# HominiPulseSensor.net
KiCad netlist of a schematic drawn in EAGLE
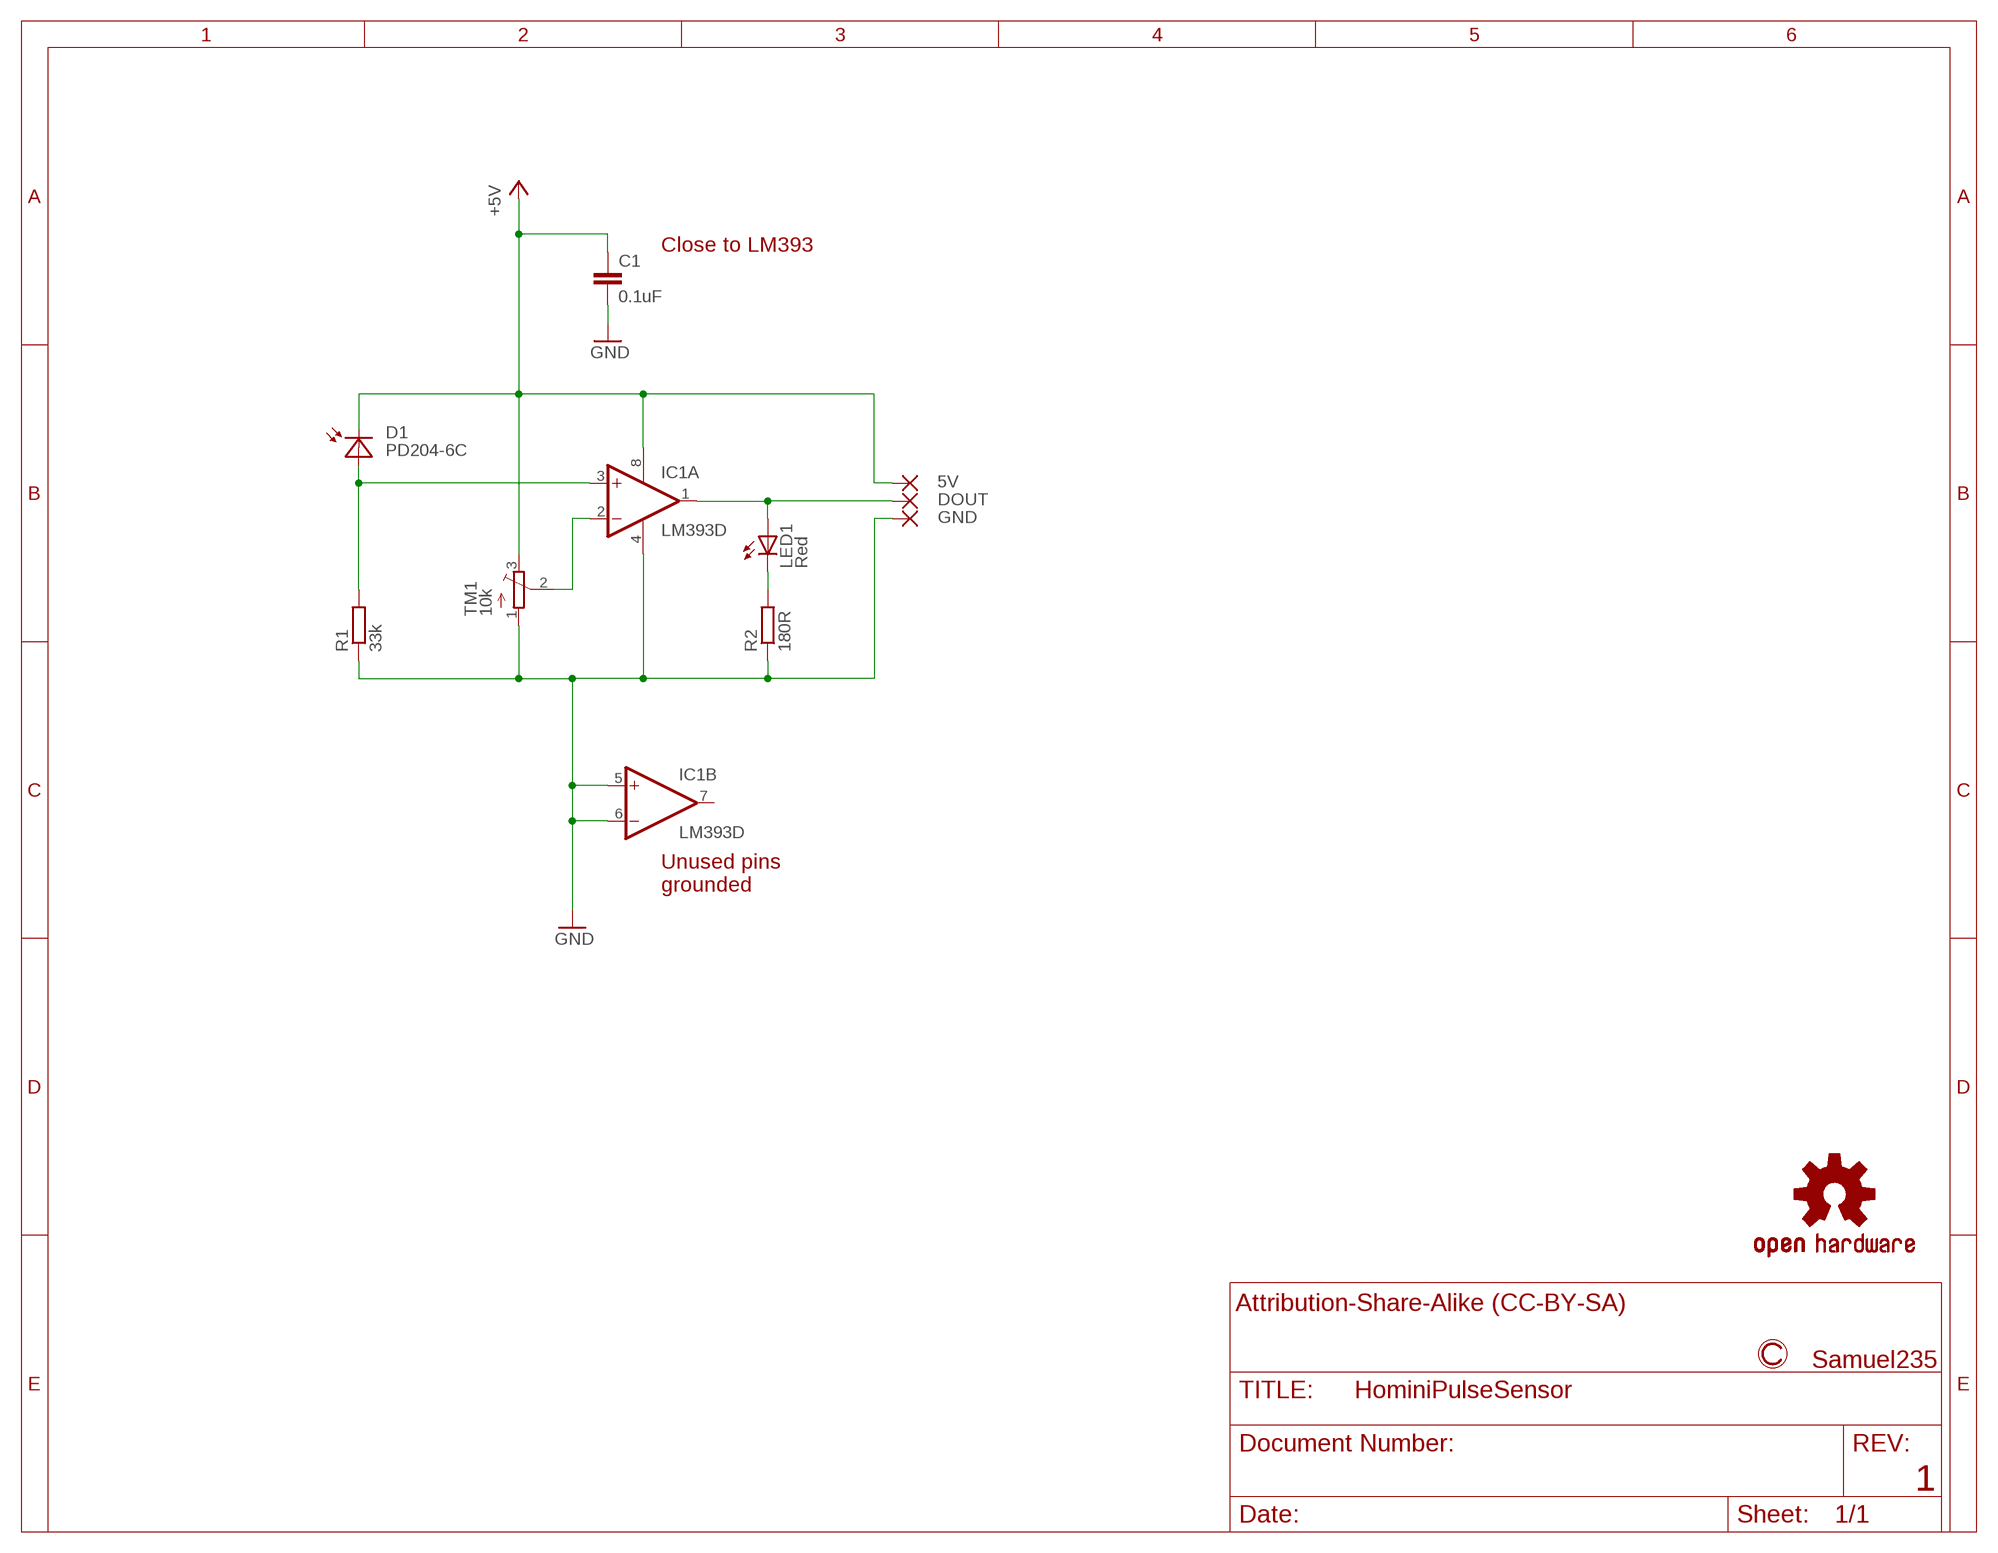
[diagram p0: schematic, sheet 1]

(export (version "E")
  (design (tool "Eeschema 10.0.6"))
  (components
    (comp (ref "5V")
      (value "SMD2")
      (footprint "eagle-import:SMD1,27-2,54")
      (libsource (lib "eagle-import") (part "SMD2"))
    )
    (comp (ref "C1")
      (value "0.1uF")
      (footprint "eagle-import:C0603")
      (libsource (lib "eagle-import") (part "C-EUC0603"))
    )
    (comp (ref "D1")
      (value "PD204-6C")
      (footprint "eagle-import:3MM-PTH")
      (libsource (lib "eagle-import") (part "PD204-6C"))
    )
    (comp (ref "DOUT")
      (value "SMD2")
      (footprint "eagle-import:SMD1,27-2,54")
      (libsource (lib "eagle-import") (part "SMD2"))
    )
    (comp (ref "GND")
      (value "SMD2")
      (footprint "eagle-import:SMD1,27-2,54")
      (libsource (lib "eagle-import") (part "SMD2"))
    )
    (comp (ref "IC1")
      (value "LM393D")
      (footprint "eagle-import:SO08")
      (libsource (lib "eagle-import") (part "LM393D"))
    )
    (comp (ref "LED1")
      (value "Red")
      (footprint "eagle-import:LED3MM")
      (libsource (lib "eagle-import") (part "LED3MM"))
    )
    (comp (ref "LOGO1")
      (value "OSHW-LOGOS")
      (footprint "eagle-import:OSHW-LOGO-S")
      (libsource (lib "eagle-import") (part "OSHW-LOGOS"))
    )
    (comp (ref "R1")
      (value "33k")
      (footprint "eagle-import:R0603")
      (libsource (lib "eagle-import") (part "R-EU_R0603"))
    )
    (comp (ref "R2")
      (value "180R")
      (footprint "eagle-import:R0603")
      (libsource (lib "eagle-import") (part "R-EU_R0603"))
    )
    (comp (ref "TM1")
      (value "10k")
      (footprint "eagle-import:TC33X")
      (libsource (lib "eagle-import") (part "TRIMPOTTC33X"))
    )
  )
  (nets
    (net (code "1") (name "+5V") (class "Default")
      (node (ref "5V") (pin "1") (pinfunction "P_1") (pintype "passive"))
      (node (ref "C1") (pin "1") (pinfunction "1_1") (pintype "passive"))
      (node (ref "D1") (pin "C") (pinfunction "C_C") (pintype "passive"))
      (node (ref "IC1") (pin "8") (pinfunction "V+_8") (pintype "power_in"))
      (node (ref "TM1") (pin "3") (pinfunction "E_3") (pintype "passive"))
    )
    (net (code "2") (name "GND") (class "Default")
      (node (ref "C1") (pin "2") (pinfunction "2_2") (pintype "passive"))
      (node (ref "GND") (pin "1") (pinfunction "P_1") (pintype "passive"))
      (node (ref "IC1") (pin "4") (pinfunction "V-_4") (pintype "power_in"))
      (node (ref "IC1") (pin "5") (pinfunction "+IN_5") (pintype "input"))
      (node (ref "IC1") (pin "6") (pinfunction "-IN_6") (pintype "input"))
      (node (ref "R1") (pin "1") (pinfunction "1_1") (pintype "passive"))
      (node (ref "R2") (pin "1") (pinfunction "1_1") (pintype "passive"))
      (node (ref "TM1") (pin "1") (pinfunction "A_1") (pintype "passive"))
    )
    (net (code "3") (name "Net-(DOUT-P)") (class "Default")
      (node (ref "DOUT") (pin "1") (pinfunction "P_1") (pintype "passive"))
      (node (ref "IC1") (pin "1") (pinfunction "OUT_1") (pintype "output"))
      (node (ref "LED1") (pin "A") (pinfunction "A_A") (pintype "passive"))
    )
    (net (code "4") (name "Net-(IC1A-+IN)") (class "Default")
      (node (ref "D1") (pin "A") (pinfunction "A_A") (pintype "passive"))
      (node (ref "IC1") (pin "3") (pinfunction "+IN_3") (pintype "input"))
      (node (ref "R1") (pin "2") (pinfunction "2_2") (pintype "passive"))
    )
    (net (code "5") (name "Net-(IC1A--IN)") (class "Default")
      (node (ref "IC1") (pin "2") (pinfunction "-IN_2") (pintype "input"))
      (node (ref "TM1") (pin "2") (pinfunction "S_2") (pintype "passive"))
    )
    (net (code "6") (name "Net-(LED1-C)") (class "Default")
      (node (ref "LED1") (pin "K") (pinfunction "C_K") (pintype "passive"))
      (node (ref "R2") (pin "2") (pinfunction "2_2") (pintype "passive"))
    )
    (net (code "7") (name "unconnected-(IC1B-OUT-Pad7)") (class "Default")
      (node (ref "IC1") (pin "7") (pinfunction "OUT_7") (pintype "output"))
    )
  )
)
